# TrinityV1_0.net
KiCad netlist of a schematic drawn in EAGLE
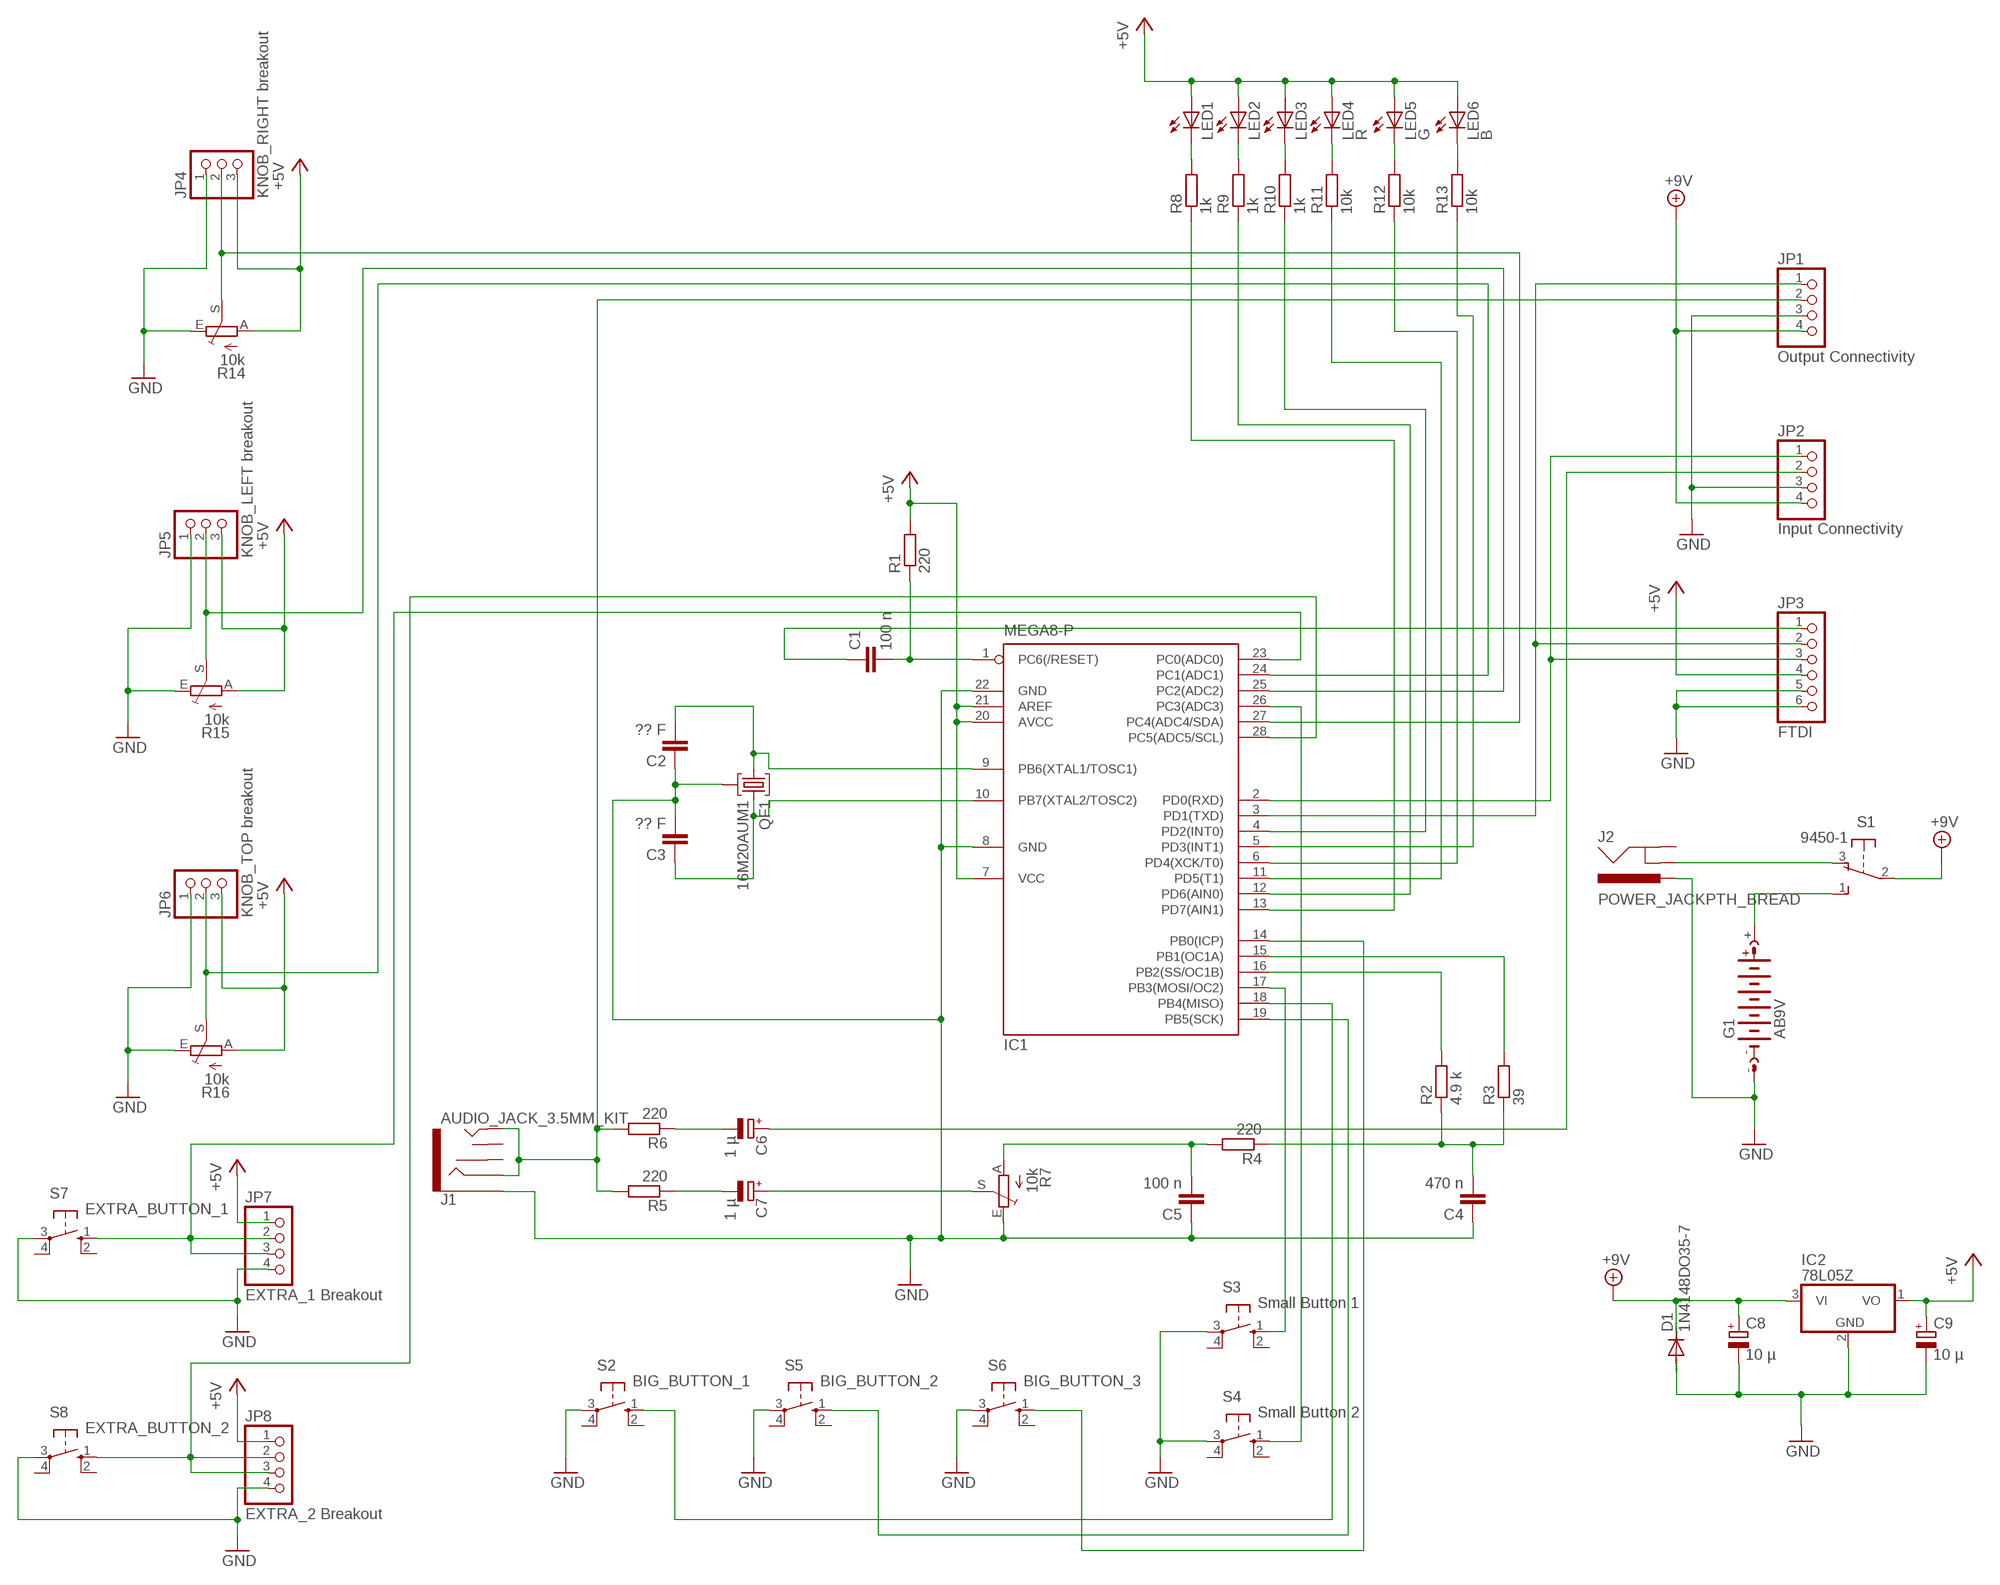
[diagram p0: schematic, sheet 1]

(export (version "E")
  (design (tool "Eeschema 10.0.6"))
  (components
    (comp (ref "C1")
      (value "100 n")
      (footprint "eagle-import:C025-030X050")
      (libsource (lib "eagle-import") (part "C-EU025-030X050"))
    )
    (comp (ref "C2")
      (value "?? F")
      (footprint "eagle-import:C025-030X050")
      (libsource (lib "eagle-import") (part "C-EU025-030X050"))
    )
    (comp (ref "C3")
      (value "?? F")
      (footprint "eagle-import:C025-030X050")
      (libsource (lib "eagle-import") (part "C-EU025-030X050"))
    )
    (comp (ref "C4")
      (value "470 n")
      (footprint "eagle-import:C025-030X050")
      (libsource (lib "eagle-import") (part "C-EU025-030X050"))
    )
    (comp (ref "C5")
      (value "100 n")
      (footprint "eagle-import:C025-030X050")
      (libsource (lib "eagle-import") (part "C-EU025-030X050"))
    )
    (comp (ref "C6")
      (value "1 µ")
      (footprint "eagle-import:E2,5-6")
      (libsource (lib "eagle-import") (part "CPOL-EUE2.5-6"))
    )
    (comp (ref "C7")
      (value "1 µ")
      (footprint "eagle-import:E2,5-6")
      (libsource (lib "eagle-import") (part "CPOL-EUE2.5-6"))
    )
    (comp (ref "C8")
      (value "10 µ")
      (footprint "eagle-import:E2,5-6")
      (libsource (lib "eagle-import") (part "CPOL-EUE2.5-6"))
    )
    (comp (ref "C9")
      (value "10 µ")
      (footprint "eagle-import:E2,5-6")
      (libsource (lib "eagle-import") (part "CPOL-EUE2.5-6"))
    )
    (comp (ref "D1")
      (value "1N4148DO35-7")
      (footprint "eagle-import:DO35-7")
      (libsource (lib "eagle-import") (part "1N4148DO35-7"))
    )
    (comp (ref "G1")
      (value "AB9V")
      (footprint "eagle-import:AB9V")
      (libsource (lib "eagle-import") (part "AB9V"))
    )
    (comp (ref "IC1")
      (value "MEGA8-P")
      (footprint "eagle-import:DIL28-3")
      (libsource (lib "eagle-import") (part "MEGA8-P"))
    )
    (comp (ref "IC2")
      (value "78L05Z")
      (footprint "eagle-import:TO92")
      (libsource (lib "eagle-import") (part "78ZL05"))
    )
    (comp (ref "J1")
      (value "AUDIO_JACK_3.5MM_KIT")
      (footprint "eagle-import:AUDIO-JACK-KIT")
      (libsource (lib "eagle-import") (part "AUDIO_JACK_3.5MM_KIT"))
    )
    (comp (ref "J2")
      (value "POWER_JACKPTH_BREAD")
      (footprint "eagle-import:POWER_JACK_PTH_BREAD")
      (libsource (lib "eagle-import") (part "POWER_JACKPTH_BREAD"))
    )
    (comp (ref "JP1")
      (value "Output Connectivity")
      (footprint "eagle-import:1X04")
      (libsource (lib "eagle-import") (part "PINHD-1X4"))
    )
    (comp (ref "JP2")
      (value "Input Connectivity")
      (footprint "eagle-import:1X04")
      (libsource (lib "eagle-import") (part "PINHD-1X4"))
    )
    (comp (ref "JP3")
      (value "FTDI")
      (footprint "eagle-import:1X06")
      (libsource (lib "eagle-import") (part "PINHD-1X6"))
    )
    (comp (ref "JP4")
      (value "KNOB_RIGHT breakout")
      (footprint "eagle-import:1X03")
      (libsource (lib "eagle-import") (part "PINHD-1X3"))
    )
    (comp (ref "JP5")
      (value "KNOB_LEFT breakout")
      (footprint "eagle-import:1X03")
      (libsource (lib "eagle-import") (part "PINHD-1X3"))
    )
    (comp (ref "JP6")
      (value "KNOB_TOP breakout")
      (footprint "eagle-import:1X03")
      (libsource (lib "eagle-import") (part "PINHD-1X3"))
    )
    (comp (ref "JP7")
      (value "EXTRA_1 Breakout")
      (footprint "eagle-import:1X04")
      (libsource (lib "eagle-import") (part "PINHD-1X4"))
    )
    (comp (ref "JP8")
      (value "EXTRA_2 Breakout")
      (footprint "eagle-import:1X04")
      (libsource (lib "eagle-import") (part "PINHD-1X4"))
    )
    (comp (ref "LED1")
      (value "LED5MM")
      (footprint "eagle-import:LED5MM")
      (libsource (lib "eagle-import") (part "LED5MM"))
    )
    (comp (ref "LED2")
      (value "LED5MM")
      (footprint "eagle-import:LED5MM")
      (libsource (lib "eagle-import") (part "LED5MM"))
    )
    (comp (ref "LED3")
      (value "LED5MM")
      (footprint "eagle-import:LED5MM")
      (libsource (lib "eagle-import") (part "LED5MM"))
    )
    (comp (ref "LED4")
      (value "R")
      (footprint "eagle-import:LED5MM")
      (libsource (lib "eagle-import") (part "LED5MM"))
    )
    (comp (ref "LED5")
      (value "G")
      (footprint "eagle-import:LED5MM")
      (libsource (lib "eagle-import") (part "LED5MM"))
    )
    (comp (ref "LED6")
      (value "B")
      (footprint "eagle-import:LED5MM")
      (libsource (lib "eagle-import") (part "LED5MM"))
    )
    (comp (ref "QF1")
      (value "16M20AUM1")
      (footprint "eagle-import:UM1")
      (libsource (lib "eagle-import") (part "16M20AUM1"))
    )
    (comp (ref "R1")
      (value "220")
      (footprint "eagle-import:0204_7")
      (libsource (lib "eagle-import") (part "R-EU_0204/7"))
    )
    (comp (ref "R2")
      (value "4.9 k")
      (footprint "eagle-import:0204_7")
      (libsource (lib "eagle-import") (part "R-EU_0204/7"))
    )
    (comp (ref "R3")
      (value "39")
      (footprint "eagle-import:0204_7")
      (libsource (lib "eagle-import") (part "R-EU_0204/7"))
    )
    (comp (ref "R4")
      (value "220")
      (footprint "eagle-import:0204_7")
      (libsource (lib "eagle-import") (part "R-EU_0204/7"))
    )
    (comp (ref "R5")
      (value "220")
      (footprint "eagle-import:0204_7")
      (libsource (lib "eagle-import") (part "R-EU_0204/7"))
    )
    (comp (ref "R6")
      (value "220")
      (footprint "eagle-import:0204_7")
      (libsource (lib "eagle-import") (part "R-EU_0204/7"))
    )
    (comp (ref "R7")
      (value "10k")
      (footprint "eagle-import:B25U")
      (libsource (lib "eagle-import") (part "TRIM_EU-B25U"))
    )
    (comp (ref "R8")
      (value "1k")
      (footprint "eagle-import:0204_7")
      (libsource (lib "eagle-import") (part "R-EU_0204/7"))
    )
    (comp (ref "R9")
      (value "1k")
      (footprint "eagle-import:0204_7")
      (libsource (lib "eagle-import") (part "R-EU_0204/7"))
    )
    (comp (ref "R10")
      (value "1k")
      (footprint "eagle-import:0204_7")
      (libsource (lib "eagle-import") (part "R-EU_0204/7"))
    )
    (comp (ref "R11")
      (value "10k")
      (footprint "eagle-import:0204_7")
      (libsource (lib "eagle-import") (part "R-EU_0204/7"))
    )
    (comp (ref "R12")
      (value "10k")
      (footprint "eagle-import:0204_7")
      (libsource (lib "eagle-import") (part "R-EU_0204/7"))
    )
    (comp (ref "R13")
      (value "10k")
      (footprint "eagle-import:0204_7")
      (libsource (lib "eagle-import") (part "R-EU_0204/7"))
    )
    (comp (ref "R14")
      (value "10k")
      (footprint "eagle-import:B25U")
      (libsource (lib "eagle-import") (part "TRIM_EU-B25U"))
    )
    (comp (ref "R15")
      (value "10k")
      (footprint "eagle-import:B25U")
      (libsource (lib "eagle-import") (part "TRIM_EU-B25U"))
    )
    (comp (ref "R16")
      (value "10k")
      (footprint "eagle-import:B25U")
      (libsource (lib "eagle-import") (part "TRIM_EU-B25U"))
    )
    (comp (ref "S1")
      (value "9450-1")
      (footprint "eagle-import:9450-1")
      (libsource (lib "eagle-import") (part "9450-1"))
    )
    (comp (ref "S2")
      (value "BIG_BUTTON_1")
      (footprint "eagle-import:B3F-40XX")
      (fields (field (name "MF") "OMRON COMPONENTS USA") (field (name "MPN") "B3F-4000"))
      (libsource (lib "eagle-import") (part "40-XX"))
    )
    (comp (ref "S3")
      (value "Small Button 1")
      (footprint "eagle-import:B3F-10XX")
      (fields (field (name "MPN") "B3F-1000"))
      (libsource (lib "eagle-import") (part "10-XX"))
    )
    (comp (ref "S4")
      (value "Small Button 2")
      (footprint "eagle-import:B3F-10XX")
      (fields (field (name "MPN") "B3F-1000"))
      (libsource (lib "eagle-import") (part "10-XX"))
    )
    (comp (ref "S5")
      (value "BIG_BUTTON_2")
      (footprint "eagle-import:B3F-40XX")
      (fields (field (name "MF") "OMRON COMPONENTS USA") (field (name "MPN") "B3F-4000"))
      (libsource (lib "eagle-import") (part "40-XX"))
    )
    (comp (ref "S6")
      (value "BIG_BUTTON_3")
      (footprint "eagle-import:B3F-40XX")
      (fields (field (name "MF") "OMRON COMPONENTS USA") (field (name "MPN") "B3F-4000"))
      (libsource (lib "eagle-import") (part "40-XX"))
    )
    (comp (ref "S7")
      (value "EXTRA_BUTTON_1")
      (footprint "eagle-import:B3F-10XX")
      (fields (field (name "MPN") "B3F-1000"))
      (libsource (lib "eagle-import") (part "10-XX"))
    )
    (comp (ref "S8")
      (value "EXTRA_BUTTON_2")
      (footprint "eagle-import:B3F-10XX")
      (fields (field (name "MPN") "B3F-1000"))
      (libsource (lib "eagle-import") (part "10-XX"))
    )
  )
  (nets
    (net (code "1") (name "+5V") (class "Default")
      (node (ref "C9") (pin "+") (pinfunction "+_+") (pintype "passive"))
      (node (ref "IC1") (pin "20") (pinfunction "AVCC_20") (pintype "power_in"))
      (node (ref "IC1") (pin "21") (pinfunction "AREF_21") (pintype "passive"))
      (node (ref "IC1") (pin "7") (pinfunction "VCC_7") (pintype "power_in"))
      (node (ref "IC2") (pin "1") (pinfunction "VO_1") (pintype "passive"))
      (node (ref "JP3") (pin "4") (pinfunction "4_4") (pintype "passive"))
      (node (ref "JP4") (pin "3") (pinfunction "3_3") (pintype "passive"))
      (node (ref "JP5") (pin "3") (pinfunction "3_3") (pintype "passive"))
      (node (ref "JP6") (pin "3") (pinfunction "3_3") (pintype "passive"))
      (node (ref "JP7") (pin "1") (pinfunction "1_1") (pintype "passive"))
      (node (ref "JP8") (pin "1") (pinfunction "1_1") (pintype "passive"))
      (node (ref "LED1") (pin "A") (pinfunction "A_A") (pintype "passive"))
      (node (ref "LED2") (pin "A") (pinfunction "A_A") (pintype "passive"))
      (node (ref "LED3") (pin "A") (pinfunction "A_A") (pintype "passive"))
      (node (ref "LED4") (pin "A") (pinfunction "A_A") (pintype "passive"))
      (node (ref "LED5") (pin "A") (pinfunction "A_A") (pintype "passive"))
      (node (ref "LED6") (pin "A") (pinfunction "A_A") (pintype "passive"))
      (node (ref "R1") (pin "2") (pinfunction "2_2") (pintype "passive"))
      (node (ref "R14") (pin "A") (pinfunction "A_A") (pintype "passive"))
      (node (ref "R15") (pin "A") (pinfunction "A_A") (pintype "passive"))
      (node (ref "R16") (pin "A") (pinfunction "A_A") (pintype "passive"))
    )
    (net (code "2") (name "+9V") (class "Default")
      (node (ref "C8") (pin "+") (pinfunction "+_+") (pintype "passive"))
      (node (ref "D1") (pin "C") (pinfunction "C_C") (pintype "passive"))
      (node (ref "IC2") (pin "3") (pinfunction "VI_3") (pintype "input"))
      (node (ref "JP1") (pin "4") (pinfunction "4_4") (pintype "passive"))
      (node (ref "JP2") (pin "4") (pinfunction "4_4") (pintype "passive"))
      (node (ref "S1") (pin "2") (pinfunction "P_2") (pintype "passive"))
    )
    (net (code "3") (name "GND") (class "Default")
      (node (ref "C2") (pin "1") (pinfunction "1_1") (pintype "passive"))
      (node (ref "C3") (pin "2") (pinfunction "2_2") (pintype "passive"))
      (node (ref "C4") (pin "1") (pinfunction "1_1") (pintype "passive"))
      (node (ref "C5") (pin "1") (pinfunction "1_1") (pintype "passive"))
      (node (ref "C8") (pin "-") (pinfunction "-_-") (pintype "passive"))
      (node (ref "C9") (pin "-") (pinfunction "-_-") (pintype "passive"))
      (node (ref "D1") (pin "A") (pinfunction "A_A") (pintype "passive"))
      (node (ref "G1") (pin "-") (pinfunction "-_-") (pintype "passive"))
      (node (ref "IC1") (pin "22") (pinfunction "GND_22") (pintype "power_in"))
      (node (ref "IC1") (pin "8") (pinfunction "GND_8") (pintype "power_in"))
      (node (ref "IC2") (pin "2") (pinfunction "GND_2") (pintype "passive"))
      (node (ref "J1") (pin "SLEEVE") (pinfunction "SLEEVE_SLEEVE") (pintype "bidirectional"))
      (node (ref "J2") (pin "PWR") (pinfunction "PWR_PWR") (pintype "bidirectional"))
      (node (ref "JP1") (pin "3") (pinfunction "3_3") (pintype "passive"))
      (node (ref "JP2") (pin "3") (pinfunction "3_3") (pintype "passive"))
      (node (ref "JP3") (pin "5") (pinfunction "5_5") (pintype "passive"))
      (node (ref "JP3") (pin "6") (pinfunction "6_6") (pintype "passive"))
      (node (ref "JP4") (pin "1") (pinfunction "1_1") (pintype "passive"))
      (node (ref "JP5") (pin "1") (pinfunction "1_1") (pintype "passive"))
      (node (ref "JP6") (pin "1") (pinfunction "1_1") (pintype "passive"))
      (node (ref "JP7") (pin "4") (pinfunction "4_4") (pintype "passive"))
      (node (ref "JP8") (pin "4") (pinfunction "4_4") (pintype "passive"))
      (node (ref "QF1") (pin "2") (pinfunction "2_2") (pintype "passive"))
      (node (ref "R14") (pin "E") (pinfunction "E_E") (pintype "passive"))
      (node (ref "R15") (pin "E") (pinfunction "E_E") (pintype "passive"))
      (node (ref "R16") (pin "E") (pinfunction "E_E") (pintype "passive"))
      (node (ref "R7") (pin "E") (pinfunction "E_E") (pintype "passive"))
      (node (ref "S2") (pin "3") (pinfunction "P_3") (pintype "passive"))
      (node (ref "S3") (pin "3") (pinfunction "P_3") (pintype "passive"))
      (node (ref "S4") (pin "3") (pinfunction "P_3") (pintype "passive"))
      (node (ref "S5") (pin "3") (pinfunction "P_3") (pintype "passive"))
      (node (ref "S6") (pin "3") (pinfunction "P_3") (pintype "passive"))
      (node (ref "S7") (pin "3") (pinfunction "P_3") (pintype "passive"))
      (node (ref "S8") (pin "3") (pinfunction "P_3") (pintype "passive"))
    )
    (net (code "4") (name "Net-(C1-Pad1)") (class "Default")
      (node (ref "C1") (pin "1") (pinfunction "1_1") (pintype "passive"))
      (node (ref "JP3") (pin "1") (pinfunction "1_1") (pintype "passive"))
    )
    (net (code "5") (name "Net-(C4-Pad2)") (class "Default")
      (node (ref "C4") (pin "2") (pinfunction "2_2") (pintype "passive"))
      (node (ref "R2") (pin "1") (pinfunction "1_1") (pintype "passive"))
      (node (ref "R3") (pin "1") (pinfunction "1_1") (pintype "passive"))
      (node (ref "R4") (pin "1") (pinfunction "1_1") (pintype "passive"))
    )
    (net (code "6") (name "Net-(C5-Pad2)") (class "Default")
      (node (ref "C5") (pin "2") (pinfunction "2_2") (pintype "passive"))
      (node (ref "R4") (pin "2") (pinfunction "2_2") (pintype "passive"))
      (node (ref "R7") (pin "A") (pinfunction "A_A") (pintype "passive"))
    )
    (net (code "7") (name "Net-(C6-Pad+)") (class "Default")
      (node (ref "C6") (pin "+") (pinfunction "+_+") (pintype "passive"))
      (node (ref "JP2") (pin "2") (pinfunction "2_2") (pintype "passive"))
    )
    (net (code "8") (name "Net-(C6-Pad-)") (class "Default")
      (node (ref "C6") (pin "-") (pinfunction "-_-") (pintype "passive"))
      (node (ref "R6") (pin "1") (pinfunction "1_1") (pintype "passive"))
    )
    (net (code "9") (name "Net-(C7-Pad+)") (class "Default")
      (node (ref "C7") (pin "+") (pinfunction "+_+") (pintype "passive"))
      (node (ref "R7") (pin "S") (pinfunction "S_S") (pintype "passive"))
    )
    (net (code "10") (name "Net-(C7-Pad-)") (class "Default")
      (node (ref "C7") (pin "-") (pinfunction "-_-") (pintype "passive"))
      (node (ref "R5") (pin "1") (pinfunction "1_1") (pintype "passive"))
    )
    (net (code "11") (name "Net-(IC1-PB0(ICP))") (class "Default")
      (node (ref "IC1") (pin "14") (pinfunction "PB0(ICP)_14") (pintype "bidirectional"))
      (node (ref "S6") (pin "1") (pinfunction "S_1") (pintype "passive"))
    )
    (net (code "12") (name "Net-(IC1-PB1(OC1A))") (class "Default")
      (node (ref "IC1") (pin "15") (pinfunction "PB1(OC1A)_15") (pintype "bidirectional"))
      (node (ref "R3") (pin "2") (pinfunction "2_2") (pintype "passive"))
    )
    (net (code "13") (name "Net-(IC1-PB2(SS{slash}OC1B))") (class "Default")
      (node (ref "IC1") (pin "16") (pinfunction "PB2(SS/OC1B)_16") (pintype "bidirectional"))
      (node (ref "R2") (pin "2") (pinfunction "2_2") (pintype "passive"))
    )
    (net (code "14") (name "Net-(IC1-PB3(MOSI{slash}OC2))") (class "Default")
      (node (ref "IC1") (pin "17") (pinfunction "PB3(MOSI/OC2)_17") (pintype "bidirectional"))
      (node (ref "S3") (pin "1") (pinfunction "S_1") (pintype "passive"))
    )
    (net (code "15") (name "Net-(IC1-PB4(MISO))") (class "Default")
      (node (ref "IC1") (pin "18") (pinfunction "PB4(MISO)_18") (pintype "bidirectional"))
      (node (ref "S2") (pin "1") (pinfunction "S_1") (pintype "passive"))
    )
    (net (code "16") (name "Net-(IC1-PB5(SCK))") (class "Default")
      (node (ref "IC1") (pin "19") (pinfunction "PB5(SCK)_19") (pintype "bidirectional"))
      (node (ref "S5") (pin "1") (pinfunction "S_1") (pintype "passive"))
    )
    (net (code "17") (name "Net-(IC1-PB6(XTAL1{slash}TOSC1))") (class "Default")
      (node (ref "C2") (pin "2") (pinfunction "2_2") (pintype "passive"))
      (node (ref "IC1") (pin "9") (pinfunction "PB6(XTAL1/TOSC1)_9") (pintype "bidirectional"))
      (node (ref "QF1") (pin "1") (pinfunction "1_1") (pintype "passive"))
    )
    (net (code "18") (name "Net-(IC1-PB7(XTAL2{slash}TOSC2))") (class "Default")
      (node (ref "C3") (pin "1") (pinfunction "1_1") (pintype "passive"))
      (node (ref "IC1") (pin "10") (pinfunction "PB7(XTAL2/TOSC2)_10") (pintype "bidirectional"))
      (node (ref "QF1") (pin "3") (pinfunction "3_3") (pintype "passive"))
    )
    (net (code "19") (name "Net-(IC1-PC0(ADC0))") (class "Default")
      (node (ref "IC1") (pin "23") (pinfunction "PC0(ADC0)_23") (pintype "bidirectional"))
      (node (ref "JP7") (pin "2") (pinfunction "2_2") (pintype "passive"))
      (node (ref "JP7") (pin "3") (pinfunction "3_3") (pintype "passive"))
      (node (ref "S7") (pin "1") (pinfunction "S_1") (pintype "passive"))
    )
    (net (code "20") (name "Net-(IC1-PC1(ADC1))") (class "Default")
      (node (ref "IC1") (pin "24") (pinfunction "PC1(ADC1)_24") (pintype "bidirectional"))
      (node (ref "JP6") (pin "2") (pinfunction "2_2") (pintype "passive"))
      (node (ref "R16") (pin "S") (pinfunction "S_S") (pintype "passive"))
    )
    (net (code "21") (name "Net-(IC1-PC2(ADC2))") (class "Default")
      (node (ref "IC1") (pin "25") (pinfunction "PC2(ADC2)_25") (pintype "bidirectional"))
      (node (ref "JP5") (pin "2") (pinfunction "2_2") (pintype "passive"))
      (node (ref "R15") (pin "S") (pinfunction "S_S") (pintype "passive"))
    )
    (net (code "22") (name "Net-(IC1-PC3(ADC3))") (class "Default")
      (node (ref "IC1") (pin "26") (pinfunction "PC3(ADC3)_26") (pintype "bidirectional"))
      (node (ref "S4") (pin "1") (pinfunction "S_1") (pintype "passive"))
    )
    (net (code "23") (name "Net-(IC1-PC4(ADC4{slash}SDA))") (class "Default")
      (node (ref "IC1") (pin "27") (pinfunction "PC4(ADC4/SDA)_27") (pintype "bidirectional"))
      (node (ref "JP4") (pin "2") (pinfunction "2_2") (pintype "passive"))
      (node (ref "R14") (pin "S") (pinfunction "S_S") (pintype "passive"))
    )
    (net (code "24") (name "Net-(IC1-PC5(ADC5{slash}SCL))") (class "Default")
      (node (ref "IC1") (pin "28") (pinfunction "PC5(ADC5/SCL)_28") (pintype "bidirectional"))
      (node (ref "JP8") (pin "2") (pinfunction "2_2") (pintype "passive"))
      (node (ref "JP8") (pin "3") (pinfunction "3_3") (pintype "passive"))
      (node (ref "S8") (pin "1") (pinfunction "S_1") (pintype "passive"))
    )
    (net (code "25") (name "Net-(IC1-PC6({slash}RESET))") (class "Default")
      (node (ref "C1") (pin "2") (pinfunction "2_2") (pintype "passive"))
      (node (ref "IC1") (pin "1") (pinfunction "PC6(/RESET)_1") (pintype "bidirectional"))
      (node (ref "R1") (pin "1") (pinfunction "1_1") (pintype "passive"))
    )
    (net (code "26") (name "Net-(IC1-PD0(RXD))") (class "Default")
      (node (ref "IC1") (pin "2") (pinfunction "PD0(RXD)_2") (pintype "bidirectional"))
      (node (ref "JP2") (pin "1") (pinfunction "1_1") (pintype "passive"))
      (node (ref "JP3") (pin "3") (pinfunction "3_3") (pintype "passive"))
    )
    (net (code "27") (name "Net-(IC1-PD1(TXD))") (class "Default")
      (node (ref "IC1") (pin "3") (pinfunction "PD1(TXD)_3") (pintype "bidirectional"))
      (node (ref "JP1") (pin "1") (pinfunction "1_1") (pintype "passive"))
      (node (ref "JP3") (pin "2") (pinfunction "2_2") (pintype "passive"))
    )
    (net (code "28") (name "Net-(IC1-PD2(INT0))") (class "Default")
      (node (ref "IC1") (pin "4") (pinfunction "PD2(INT0)_4") (pintype "bidirectional"))
      (node (ref "R10") (pin "1") (pinfunction "1_1") (pintype "passive"))
    )
    (net (code "29") (name "Net-(IC1-PD3(INT1))") (class "Default")
      (node (ref "IC1") (pin "5") (pinfunction "PD3(INT1)_5") (pintype "bidirectional"))
      (node (ref "R13") (pin "1") (pinfunction "1_1") (pintype "passive"))
    )
    (net (code "30") (name "Net-(IC1-PD4(XCK{slash}T0))") (class "Default")
      (node (ref "IC1") (pin "6") (pinfunction "PD4(XCK/T0)_6") (pintype "bidirectional"))
      (node (ref "R12") (pin "1") (pinfunction "1_1") (pintype "passive"))
    )
    (net (code "31") (name "Net-(IC1-PD5(T1))") (class "Default")
      (node (ref "IC1") (pin "11") (pinfunction "PD5(T1)_11") (pintype "bidirectional"))
      (node (ref "R11") (pin "1") (pinfunction "1_1") (pintype "passive"))
    )
    (net (code "32") (name "Net-(IC1-PD6(AIN0))") (class "Default")
      (node (ref "IC1") (pin "12") (pinfunction "PD6(AIN0)_12") (pintype "bidirectional"))
      (node (ref "R9") (pin "1") (pinfunction "1_1") (pintype "passive"))
    )
    (net (code "33") (name "Net-(IC1-PD7(AIN1))") (class "Default")
      (node (ref "IC1") (pin "13") (pinfunction "PD7(AIN1)_13") (pintype "bidirectional"))
      (node (ref "R8") (pin "1") (pinfunction "1_1") (pintype "passive"))
    )
    (net (code "34") (name "Net-(J1-PadRING)") (class "Default")
      (node (ref "J1") (pin "RING") (pinfunction "RING_RING") (pintype "bidirectional"))
      (node (ref "J1") (pin "TIP") (pinfunction "TIP_TIP") (pintype "bidirectional"))
      (node (ref "JP1") (pin "2") (pinfunction "2_2") (pintype "passive"))
      (node (ref "R5") (pin "2") (pinfunction "2_2") (pintype "passive"))
      (node (ref "R6") (pin "2") (pinfunction "2_2") (pintype "passive"))
    )
    (net (code "35") (name "Net-(LED1-C)") (class "Default")
      (node (ref "LED1") (pin "K") (pinfunction "C_K") (pintype "passive"))
      (node (ref "R8") (pin "2") (pinfunction "2_2") (pintype "passive"))
    )
    (net (code "36") (name "Net-(LED2-C)") (class "Default")
      (node (ref "LED2") (pin "K") (pinfunction "C_K") (pintype "passive"))
      (node (ref "R9") (pin "2") (pinfunction "2_2") (pintype "passive"))
    )
    (net (code "37") (name "Net-(LED3-C)") (class "Default")
      (node (ref "LED3") (pin "K") (pinfunction "C_K") (pintype "passive"))
      (node (ref "R10") (pin "2") (pinfunction "2_2") (pintype "passive"))
    )
    (net (code "38") (name "Net-(LED4-C)") (class "Default")
      (node (ref "LED4") (pin "K") (pinfunction "C_K") (pintype "passive"))
      (node (ref "R11") (pin "2") (pinfunction "2_2") (pintype "passive"))
    )
    (net (code "39") (name "Net-(LED5-C)") (class "Default")
      (node (ref "LED5") (pin "K") (pinfunction "C_K") (pintype "passive"))
      (node (ref "R12") (pin "2") (pinfunction "2_2") (pintype "passive"))
    )
    (net (code "40") (name "Net-(LED6-C)") (class "Default")
      (node (ref "LED6") (pin "K") (pinfunction "C_K") (pintype "passive"))
      (node (ref "R13") (pin "2") (pinfunction "2_2") (pintype "passive"))
    )
    (net (code "41") (name "Net-(S1-O)") (class "Default")
      (node (ref "J2") (pin "GNDBREAK") (pinfunction "GNDBREAK_GNDBREAK") (pintype "bidirectional"))
      (node (ref "S1") (pin "3") (pinfunction "O_3") (pintype "passive"))
    )
    (net (code "42") (name "Net-(S1-S)") (class "Default")
      (node (ref "G1") (pin "+") (pinfunction "+_+") (pintype "passive"))
      (node (ref "S1") (pin "1") (pinfunction "S_1") (pintype "passive"))
    )
    (net (code "43") (name "unconnected-(J1-PadRSH)") (class "Default")
      (node (ref "J1") (pin "RSH") (pinfunction "RSH_RSH") (pintype "bidirectional"))
    )
    (net (code "44") (name "unconnected-(J1-PadTSH)") (class "Default")
      (node (ref "J1") (pin "TSH") (pinfunction "TSH_TSH") (pintype "bidirectional"))
    )
    (net (code "45") (name "unconnected-(J2-PadGND)") (class "Default")
      (node (ref "J2") (pin "GND") (pinfunction "GND_GND") (pintype "bidirectional"))
    )
    (net (code "46") (name "unconnected-(S2-P1-Pad4)") (class "Default")
      (node (ref "S2") (pin "4") (pinfunction "P1_4") (pintype "passive"))
    )
    (net (code "47") (name "unconnected-(S2-S1-Pad2)") (class "Default")
      (node (ref "S2") (pin "2") (pinfunction "S1_2") (pintype "passive"))
    )
    (net (code "48") (name "unconnected-(S3-P1-Pad4)") (class "Default")
      (node (ref "S3") (pin "4") (pinfunction "P1_4") (pintype "passive"))
    )
    (net (code "49") (name "unconnected-(S3-S1-Pad2)") (class "Default")
      (node (ref "S3") (pin "2") (pinfunction "S1_2") (pintype "passive"))
    )
    (net (code "50") (name "unconnected-(S4-P1-Pad4)") (class "Default")
      (node (ref "S4") (pin "4") (pinfunction "P1_4") (pintype "passive"))
    )
    (net (code "51") (name "unconnected-(S4-S1-Pad2)") (class "Default")
      (node (ref "S4") (pin "2") (pinfunction "S1_2") (pintype "passive"))
    )
    (net (code "52") (name "unconnected-(S5-P1-Pad4)") (class "Default")
      (node (ref "S5") (pin "4") (pinfunction "P1_4") (pintype "passive"))
    )
    (net (code "53") (name "unconnected-(S5-S1-Pad2)") (class "Default")
      (node (ref "S5") (pin "2") (pinfunction "S1_2") (pintype "passive"))
    )
    (net (code "54") (name "unconnected-(S6-P1-Pad4)") (class "Default")
      (node (ref "S6") (pin "4") (pinfunction "P1_4") (pintype "passive"))
    )
    (net (code "55") (name "unconnected-(S6-S1-Pad2)") (class "Default")
      (node (ref "S6") (pin "2") (pinfunction "S1_2") (pintype "passive"))
    )
    (net (code "56") (name "unconnected-(S7-P1-Pad4)") (class "Default")
      (node (ref "S7") (pin "4") (pinfunction "P1_4") (pintype "passive"))
    )
    (net (code "57") (name "unconnected-(S7-S1-Pad2)") (class "Default")
      (node (ref "S7") (pin "2") (pinfunction "S1_2") (pintype "passive"))
    )
    (net (code "58") (name "unconnected-(S8-P1-Pad4)") (class "Default")
      (node (ref "S8") (pin "4") (pinfunction "P1_4") (pintype "passive"))
    )
    (net (code "59") (name "unconnected-(S8-S1-Pad2)") (class "Default")
      (node (ref "S8") (pin "2") (pinfunction "S1_2") (pintype "passive"))
    )
  )
)
